# interfaces.net
KiCad netlist of a schematic drawn in Altium Designer
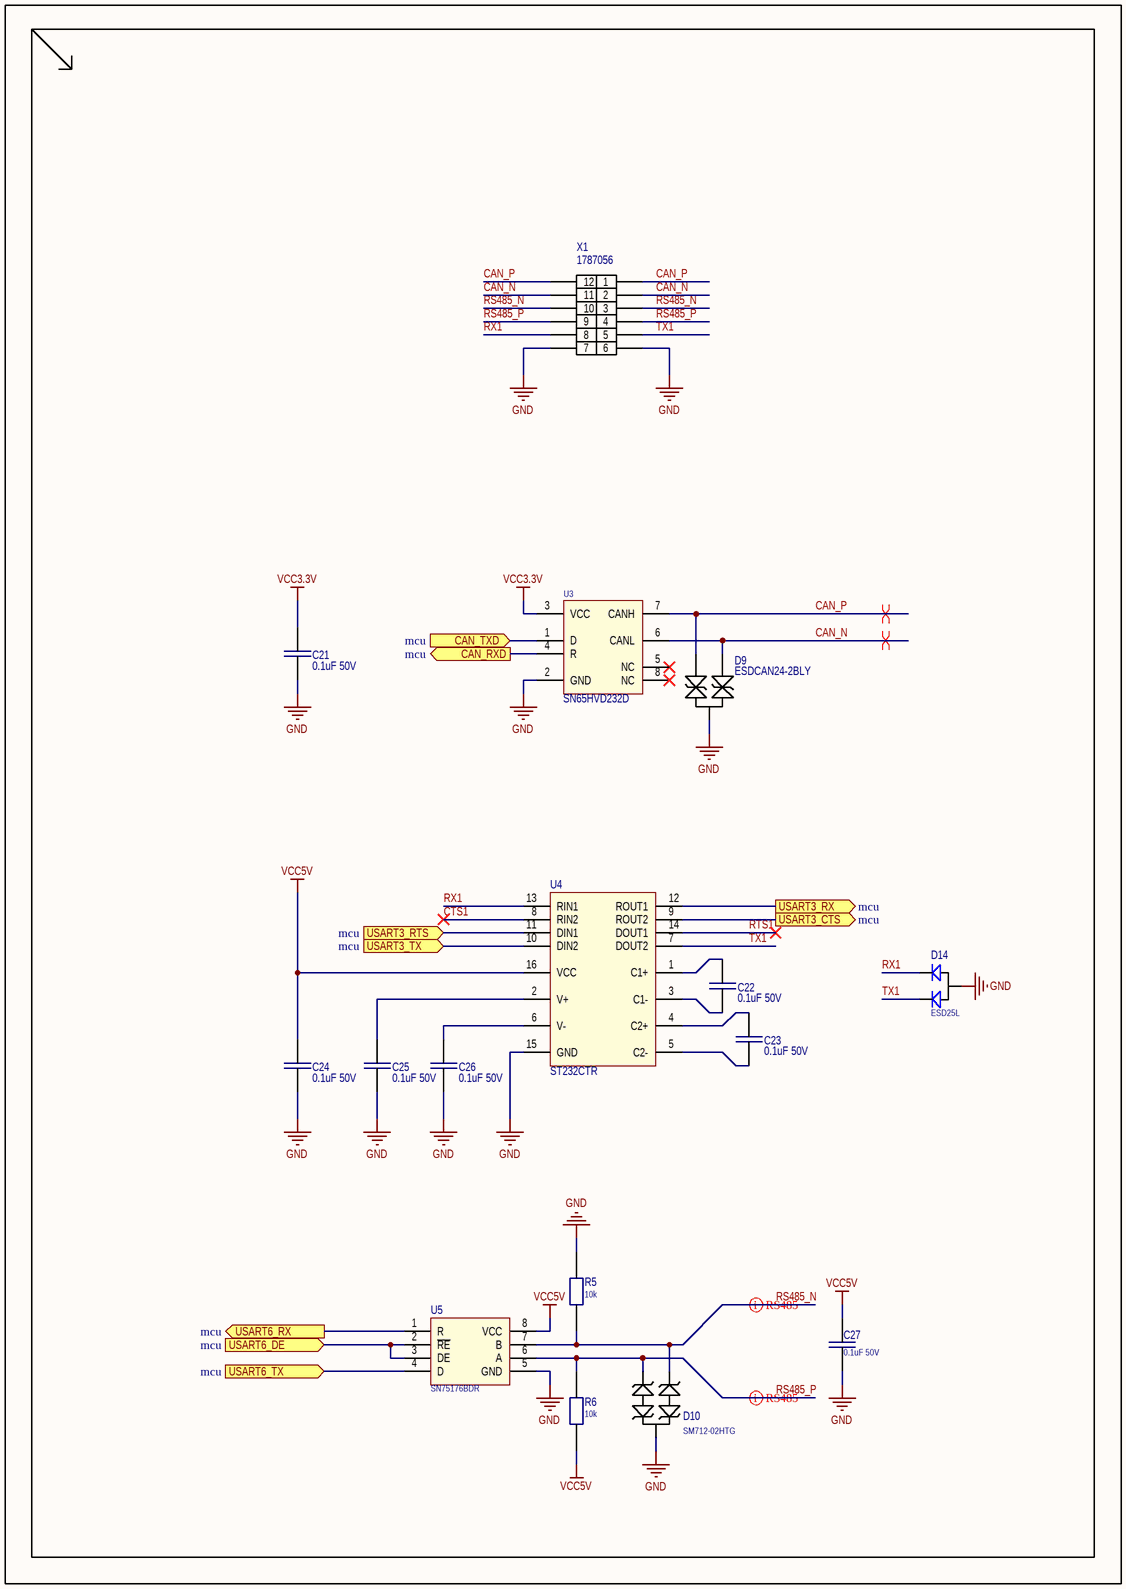
[diagram p0: interfaces.schdoc]

(export (version "E")
  (design (tool "Eeschema 10.0.6"))
  (components
    (comp (ref "C21")
      (value "0.1uF 50V")
      (footprint "C_0603")
      (description "Capacitor")
      (fields (field (name "PART") "CC0603KPX7R9BB104") (field (name "JLCPCB PART") "C14663"))
      (libsource (lib "capacitors") (part "CAP_SMD"))
    )
    (comp (ref "C22")
      (value "0.1uF 50V")
      (footprint "C_0603")
      (description "Capacitor")
      (fields (field (name "PART") "CC0603KPX7R9BB104") (field (name "JLCPCB PART") "C14663"))
      (libsource (lib "capacitors") (part "C0603"))
    )
    (comp (ref "C23")
      (value "0.1uF 50V")
      (footprint "C_0603")
      (description "Capacitor")
      (fields (field (name "PART") "CC0603KPX7R9BB104") (field (name "JLCPCB PART") "C14663"))
      (libsource (lib "capacitors") (part "C0603"))
    )
    (comp (ref "C24")
      (value "0.1uF 50V")
      (footprint "C_0603")
      (description "Capacitor")
      (fields (field (name "PART") "CC0603KPX7R9BB104") (field (name "JLCPCB PART") "C14663"))
      (libsource (lib "capacitors") (part "C0603"))
    )
    (comp (ref "C25")
      (value "0.1uF 50V")
      (footprint "C_0603")
      (description "Capacitor")
      (fields (field (name "PART") "CC0603KPX7R9BB104") (field (name "JLCPCB PART") "C14663"))
      (libsource (lib "capacitors") (part "C0603"))
    )
    (comp (ref "C26")
      (value "0.1uF 50V")
      (footprint "C_0603")
      (description "Capacitor")
      (fields (field (name "PART") "CC0603KPX7R9BB104") (field (name "JLCPCB PART") "C14663"))
      (libsource (lib "capacitors") (part "C0603"))
    )
    (comp (ref "C27")
      (value "0.1uF 50V")
      (footprint "C_0603")
      (description "Capacitor")
      (fields (field (name "PART") "CC0603KPX7R9BB104") (field (name "JLCPCB PART") "C14663"))
      (libsource (lib "capacitors") (part "CAP_SMD"))
    )
    (comp (ref "D9")
      (value "ESDCAN24-2BLY")
      (footprint "diode:SOT23")
      (description "ESD")
      (fields (field (name "JLCPCB PART") "C5158050"))
      (libsource (lib "diode") (part "ESD_CAN"))
    )
    (comp (ref "D10")
      (value "SM712-02HTG")
      (footprint "diode:SOT23")
      (description "ESD")
      (fields (field (name "JLCPCB PART") "C5449363"))
      (libsource (lib "diode") (part "ESD"))
    )
    (comp (ref "D14")
      (value "ESD25L")
      (footprint "SOT23")
      (description "Diode")
      (fields (field (name "PART") "ESDA25L") (field (name "JLCPCBPART") "C95343"))
      (libsource (lib "diode") (part "TVS_SOT23"))
    )
    (comp (ref "R5")
      (value "10k")
      (footprint "R_0603")
      (description "Resistor")
      (fields (field (name "PART") "RC0603JR-0710KL") (field (name "JLCPCB PART") "C99198"))
      (libsource (lib "resistors") (part "RES_SMD"))
    )
    (comp (ref "R6")
      (value "10k")
      (footprint "R_0603")
      (description "Resistor")
      (fields (field (name "PART") "RC0603JR-0710KL") (field (name "JLCPCB PART") "C99198"))
      (libsource (lib "resistors") (part "RES_SMD"))
    )
    (comp (ref "U3")
      (value "SN65HVD232D")
      (footprint "SO-8_M")
      (description "CAN_transiever")
      (fields (field (name "PART") "SN65HVD232DR") (field (name "JLCPCB PART") "C30530"))
      (libsource (lib "discret_ic") (part "SN65HVD232D"))
    )
    (comp (ref "U4")
      (value "ST232CTR")
      (footprint "TSSOP16_STM")
      (fields
        (field (name "JLCPCB PART") "C13482")
        (field (name "COPYRIGHT") "Copyright (C) 2022 Ultra Librarian. All rights reserved.")
      )
      (libsource (lib "discret_ic") (part "ST232CTR"))
    )
    (comp (ref "U5")
      (value "SN75176BDR")
      (footprint "SO-8")
      (description "RS485 Half Duplex Convertor")
      (fields (field (name "JLCPCB PART") "C2829048"))
      (libsource (lib "discret_ic") (part "SN75176BDR"))
    )
    (comp (ref "X1")
      (value "1787056")
      (footprint "DMC 1.5/ 6-G1F-3.5-LR P20THR 1787056")
      (description "THR-3.5-12P")
      (fields (field (name "JLCPCB PART") "C2923273"))
      (libsource (lib "connectors_socets") (part "15EDGRHCM-THR-3.5"))
    )
  )
  (nets
    (net (code "1") (name "/CAN_N") (class "Default")
      (node (ref "D9") (pin "2") (pinfunction "2_2") (pintype "passive"))
      (node (ref "U3") (pin "6") (pinfunction "CANL_6") (pintype "passive"))
      (node (ref "X1") (pin "11") (pinfunction "11_11") (pintype "passive"))
      (node (ref "X1") (pin "2") (pinfunction "2_2") (pintype "passive"))
    )
    (net (code "2") (name "/CAN_P") (class "Default")
      (node (ref "D9") (pin "1") (pinfunction "1_1") (pintype "passive"))
      (node (ref "U3") (pin "7") (pinfunction "CANH_7") (pintype "passive"))
      (node (ref "X1") (pin "1") (pinfunction "1_1") (pintype "passive"))
      (node (ref "X1") (pin "12") (pinfunction "12_12") (pintype "passive"))
    )
    (net (code "3") (name "/CAN_RXD") (class "Default")
      (node (ref "U3") (pin "4") (pinfunction "R_4") (pintype "passive"))
    )
    (net (code "4") (name "/CAN_TXD") (class "Default")
      (node (ref "U3") (pin "1") (pinfunction "D_1") (pintype "passive"))
    )
    (net (code "5") (name "/CTS1") (class "Default")
      (node (ref "U4") (pin "8") (pinfunction "RIN2_8") (pintype "passive+no_connect"))
    )
    (net (code "6") (name "/RS485_N") (class "Default")
      (node (ref "D10") (pin "1") (pinfunction "1_1") (pintype "passive"))
      (node (ref "R5") (pin "1") (pinfunction "1_1") (pintype "passive"))
      (node (ref "U5") (pin "7") (pinfunction "B_7") (pintype "passive"))
      (node (ref "X1") (pin "10") (pinfunction "10_10") (pintype "passive"))
      (node (ref "X1") (pin "3") (pinfunction "3_3") (pintype "passive"))
    )
    (net (code "7") (name "/RS485_P") (class "Default")
      (node (ref "D10") (pin "2") (pinfunction "2_2") (pintype "passive"))
      (node (ref "R6") (pin "2") (pinfunction "2_2") (pintype "passive"))
      (node (ref "U5") (pin "6") (pinfunction "A_6") (pintype "passive"))
      (node (ref "X1") (pin "4") (pinfunction "4_4") (pintype "passive"))
      (node (ref "X1") (pin "9") (pinfunction "9_9") (pintype "passive"))
    )
    (net (code "8") (name "/RTS1") (class "Default")
      (node (ref "U4") (pin "14") (pinfunction "DOUT1_14") (pintype "passive+no_connect"))
    )
    (net (code "9") (name "/RX1") (class "Default")
      (node (ref "D14") (pin "2") (pinfunction "2_2") (pintype "passive"))
      (node (ref "U4") (pin "13") (pinfunction "RIN1_13") (pintype "passive"))
      (node (ref "X1") (pin "8") (pinfunction "8_8") (pintype "passive"))
    )
    (net (code "10") (name "/TX1") (class "Default")
      (node (ref "D14") (pin "1") (pinfunction "1_1") (pintype "passive"))
      (node (ref "U4") (pin "7") (pinfunction "DOUT2_7") (pintype "passive"))
      (node (ref "X1") (pin "5") (pinfunction "5_5") (pintype "passive"))
    )
    (net (code "11") (name "/USART3_CTS") (class "Default")
      (node (ref "U4") (pin "9") (pinfunction "ROUT2_9") (pintype "passive"))
    )
    (net (code "12") (name "/USART3_RTS") (class "Default")
      (node (ref "U4") (pin "11") (pinfunction "DIN1_11") (pintype "passive"))
    )
    (net (code "13") (name "/USART3_RX") (class "Default")
      (node (ref "U4") (pin "12") (pinfunction "ROUT1_12") (pintype "passive"))
    )
    (net (code "14") (name "/USART3_TX") (class "Default")
      (node (ref "U4") (pin "10") (pinfunction "DIN2_10") (pintype "passive"))
    )
    (net (code "15") (name "/USART6_DE") (class "Default")
      (node (ref "U5") (pin "2") (pinfunction "~{RE}_2") (pintype "passive"))
      (node (ref "U5") (pin "3") (pinfunction "DE_3") (pintype "passive"))
    )
    (net (code "16") (name "/USART6_RX") (class "Default")
      (node (ref "U5") (pin "1") (pinfunction "R_1") (pintype "passive"))
    )
    (net (code "17") (name "/USART6_TX") (class "Default")
      (node (ref "U5") (pin "4") (pinfunction "D_4") (pintype "passive"))
    )
    (net (code "18") (name "GND") (class "Default")
      (node (ref "C21") (pin "1") (pinfunction "1_1") (pintype "passive"))
      (node (ref "C24") (pin "1") (pinfunction "1_1") (pintype "passive"))
      (node (ref "C25") (pin "1") (pinfunction "1_1") (pintype "passive"))
      (node (ref "C26") (pin "1") (pinfunction "1_1") (pintype "passive"))
      (node (ref "C27") (pin "1") (pinfunction "1_1") (pintype "passive"))
      (node (ref "D10") (pin "3") (pinfunction "3_3") (pintype "passive"))
      (node (ref "D14") (pin "3") (pinfunction "3_3") (pintype "passive"))
      (node (ref "D9") (pin "3") (pinfunction "3_3") (pintype "passive"))
      (node (ref "R5") (pin "2") (pinfunction "2_2") (pintype "passive"))
      (node (ref "U3") (pin "2") (pinfunction "GND_2") (pintype "passive"))
      (node (ref "U4") (pin "15") (pinfunction "GND_15") (pintype "passive"))
      (node (ref "U5") (pin "5") (pinfunction "GND_5") (pintype "passive"))
      (node (ref "X1") (pin "6") (pinfunction "6_6") (pintype "passive"))
      (node (ref "X1") (pin "7") (pinfunction "7_7") (pintype "passive"))
    )
    (net (code "19") (name "Net-(U4-C1+)") (class "Default")
      (node (ref "C22") (pin "1") (pinfunction "1_1") (pintype "passive"))
      (node (ref "U4") (pin "1") (pinfunction "C1+_1") (pintype "passive"))
    )
    (net (code "20") (name "Net-(U4-C1-)") (class "Default")
      (node (ref "C22") (pin "2") (pinfunction "2_2") (pintype "passive"))
      (node (ref "U4") (pin "3") (pinfunction "C1-_3") (pintype "passive"))
    )
    (net (code "21") (name "Net-(U4-C2+)") (class "Default")
      (node (ref "C23") (pin "1") (pinfunction "1_1") (pintype "passive"))
      (node (ref "U4") (pin "4") (pinfunction "C2+_4") (pintype "passive"))
    )
    (net (code "22") (name "Net-(U4-C2-)") (class "Default")
      (node (ref "C23") (pin "2") (pinfunction "2_2") (pintype "passive"))
      (node (ref "U4") (pin "5") (pinfunction "C2-_5") (pintype "passive"))
    )
    (net (code "23") (name "Net-(U4-V+)") (class "Default")
      (node (ref "C25") (pin "2") (pinfunction "2_2") (pintype "passive"))
      (node (ref "U4") (pin "2") (pinfunction "V+_2") (pintype "passive"))
    )
    (net (code "24") (name "Net-(U4-V-)") (class "Default")
      (node (ref "C26") (pin "2") (pinfunction "2_2") (pintype "passive"))
      (node (ref "U4") (pin "6") (pinfunction "V-_6") (pintype "passive"))
    )
    (net (code "25") (name "VCC3.3V") (class "Default")
      (node (ref "C21") (pin "2") (pinfunction "2_2") (pintype "passive"))
      (node (ref "U3") (pin "3") (pinfunction "VCC_3") (pintype "passive"))
    )
    (net (code "26") (name "VCC5V") (class "Default")
      (node (ref "C24") (pin "2") (pinfunction "2_2") (pintype "passive"))
      (node (ref "C27") (pin "2") (pinfunction "2_2") (pintype "passive"))
      (node (ref "R6") (pin "1") (pinfunction "1_1") (pintype "passive"))
      (node (ref "U4") (pin "16") (pinfunction "VCC_16") (pintype "passive"))
      (node (ref "U5") (pin "8") (pinfunction "VCC_8") (pintype "passive"))
    )
    (net (code "27") (name "unconnected-(U3-NC-Pad5)") (class "Default")
      (node (ref "U3") (pin "5") (pinfunction "NC_5") (pintype "passive+no_connect"))
    )
    (net (code "28") (name "unconnected-(U3-NC-Pad8)") (class "Default")
      (node (ref "U3") (pin "8") (pinfunction "NC_8") (pintype "passive+no_connect"))
    )
  )
)
